# 00_Power.net
KiCad netlist of a schematic drawn in Altium Designer
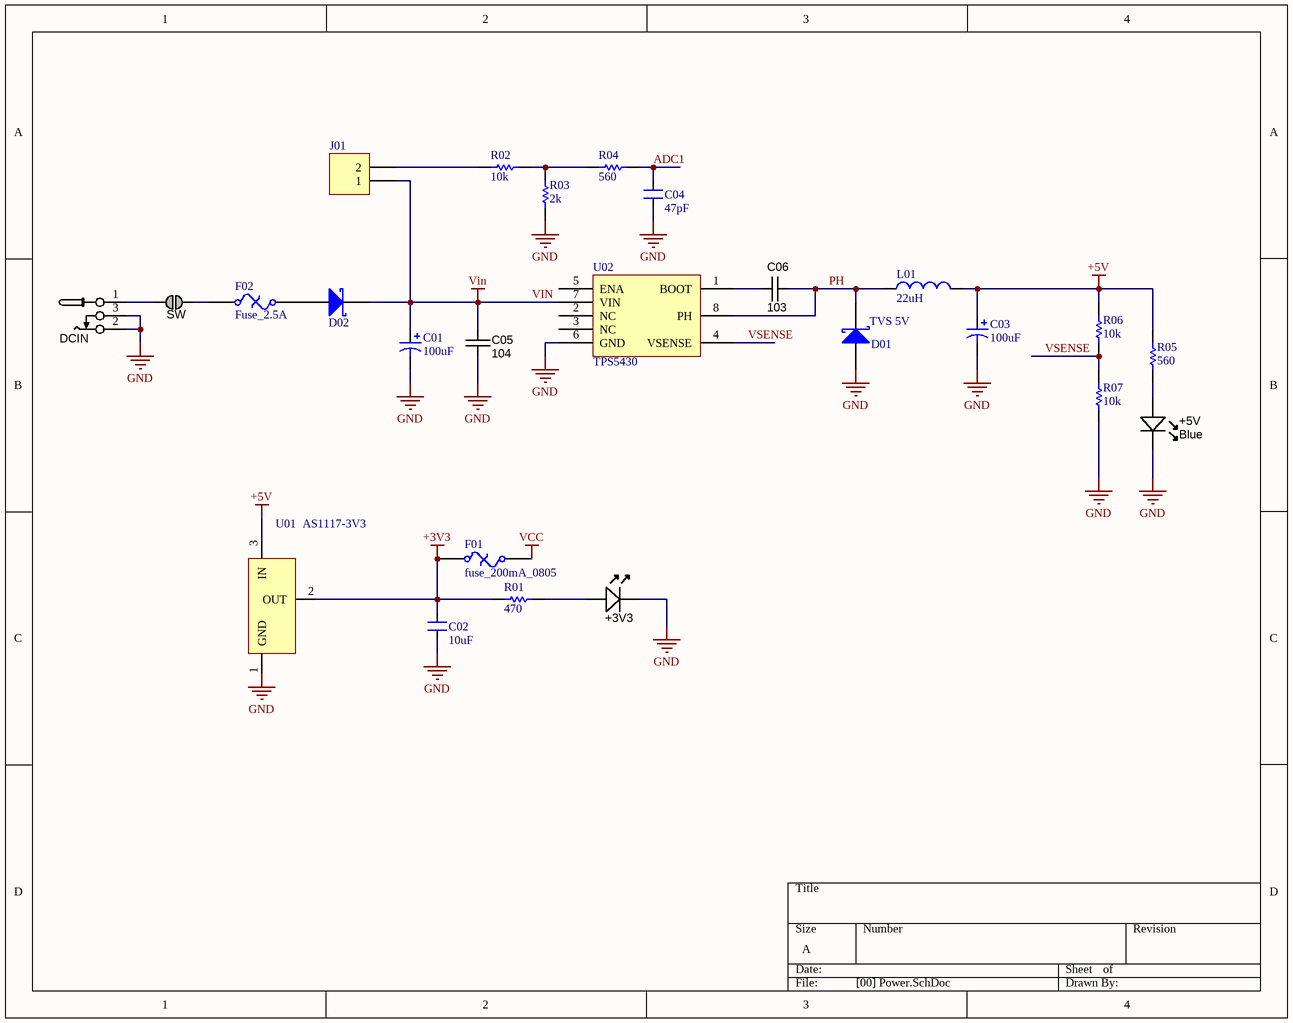
[diagram p0: [00] Power.SchDoc]

(export (version "E")
  (design (tool "Eeschema 10.0.6"))
  (components
    (comp (ref "+3V3")
      (value "Blue")
      (footprint "LED-0805-K")
      (description "LED 0805 SMD Blue 100mcd 470nm")
      (libsource (lib "PBL - Light Sources") (part "LED_SMD_Blue_0805_100mcd"))
    )
    (comp (ref "+5V")
      (value "Blue")
      (footprint "LED-0805-K")
      (description "LED 0805 SMD Blue 100mcd 470nm")
      (fields (field (name "COLOR") "Blue"))
      (libsource (lib "PBL - Light Sources") (part "LED_SMD_Blue_0805_100mcd"))
    )
    (comp (ref "C01")
      (value "100uF")
      (footprint "CAPE3.5-5.0MM_Rad_10x14mm")
      (fields (field (name "Comment") "Cap"))
      (libsource (lib "Tuan") (part "Cap"))
    )
    (comp (ref "C02")
      (value "10uF")
      (footprint "CAPMP3528X210N")
      (fields (field (name "Comment") "Cap_10uF"))
      (libsource (lib "Tuan") (part "CAP NP"))
    )
    (comp (ref "C03")
      (value "100uF")
      (footprint "CAPE3.5-5.0MM_Rad_10x14mm")
      (fields (field (name "Comment") "Cap"))
      (libsource (lib "Tuan") (part "Cap"))
    )
    (comp (ref "C04")
      (value "47pF")
      (footprint "CAPC1608N")
      (fields (field (name "Comment") "Cap_103_0603"))
      (libsource (lib "Tuan") (part "CAP NP"))
    )
    (comp (ref "C05")
      (value "104")
      (footprint "CAPC1608N")
      (description "Capacitor SMD Cer 1nF 10% 100V X7R 0603")
      (fields (field (name "TOLERANCE") "±10%") (field (name "Comment") "approved sub OK"))
      (libsource (lib "PBL - Capacitors") (part "CAPC_1n_0603_100V"))
    )
    (comp (ref "C06")
      (value "103")
      (footprint "CAPC1608N")
      (description "Capacitor SMD Cer 1nF 10% 100V X7R 0603")
      (fields (field (name "TOLERANCE") "±10%") (field (name "Comment") "approved sub OK"))
      (libsource (lib "PBL - Capacitors") (part "CAPC_1n_0603_100V"))
    )
    (comp (ref "D01") (value "TVS 5V") (footprint "SMD diode") (libsource (lib "Tuan") (part "Diode")))
    (comp (ref "D02") (value "SS14") (footprint "DO-214AC") (libsource (lib "Tuan") (part "Diode")))
    (comp (ref "DCIN")
      (value "CONN_PWR_JACK_2.1x5.5mm")
      (footprint "CONN_PWR_JACK_2.1x5.5mm")
      (description "Power Connector, THT, 2.1mm ID, 5.5mm OD")
      (libsource (lib "PBL - Connectors") (part "CONN_PWR_JACK_2.1x5.5mm"))
    )
    (comp (ref "F01")
      (value "fuse_200mA_0805")
      (footprint "SMD 1206")
      (description "Thermal Fuse")
      (fields (field (name "PUBLISHER") "Altium Limited"))
      (libsource (lib "Miscellaneous Devices") (part "Fuse Thermal"))
    )
    (comp (ref "F02")
      (value "Fuse_2.5A")
      (footprint "FUSE_SR-5-BK")
      (description "Thermal Fuse")
      (fields (field (name "PUBLISHER") "Altium Limited"))
      (libsource (lib "Miscellaneous Devices") (part "Fuse Thermal"))
    )
    (comp (ref "J01")
      (value "Header 2")
      (footprint "HDR1X2")
      (description "Header, 2-Pin")
      (fields (field (name "PUBLISHER") "Altium Limited"))
      (libsource (lib "Miscellaneous Connectors") (part "Header 2"))
    )
    (comp (ref "L01")
      (value "22uH")
      (footprint "Inductor 12x12x6")
      (fields (field (name "Comment") "Inductor"))
      (libsource (lib "Tuan") (part "Inductor"))
    )
    (comp (ref "R01")
      (value "470")
      (footprint "RESC1608N_F")
      (fields (field (name "Comment") "Res_560_0603"))
      (libsource (lib "Tuan") (part "Res"))
    )
    (comp (ref "R02")
      (value "10k")
      (footprint "RESC1608N_F")
      (fields (field (name "Comment") "Res_10k_0603"))
      (libsource (lib "Tuan") (part "Res"))
    )
    (comp (ref "R03")
      (value "2k")
      (footprint "RESC1608N_F")
      (fields (field (name "Comment") "Res_2k_0603"))
      (libsource (lib "Tuan") (part "Res"))
    )
    (comp (ref "R04")
      (value "560")
      (footprint "RESC1608N_F")
      (fields (field (name "Comment") "Res_560_0603"))
      (libsource (lib "Tuan") (part "Res"))
    )
    (comp (ref "R05")
      (value "560")
      (footprint "RESC1608N_ZERO")
      (fields (field (name "Comment") "Res"))
      (libsource (lib "Tuan") (part "Res"))
    )
    (comp (ref "R06")
      (value "10k")
      (footprint "RESC1608N_ZERO")
      (fields (field (name "Comment") "Res"))
      (libsource (lib "Tuan") (part "Res"))
    )
    (comp (ref "R07")
      (value "10k")
      (footprint "RESC1608N_ZERO")
      (fields (field (name "Comment") "Res"))
      (libsource (lib "Tuan") (part "Res"))
    )
    (comp (ref "SW")
      (value "Jumper")
      (footprint "JUMP1")
      (description "SMD jumper")
      (libsource (lib "PBL - Pads and Jumpers") (part "JUMP1"))
    )
    (comp (ref "U01") (value "AS1117-3V3") (footprint "SOT223-4N") (libsource (lib "Tuan") (part "AS1117")))
    (comp (ref "U02")
      (value "TPS5430")
      (footprint "SOIC127P600X175-8AN")
      (libsource (lib "Tuan") (part "TPS5430"))
    )
  )
  (nets
    (net (code "1") (name "+3V3") (class "Default")
      (node (ref "C02") (pin "2") (pinfunction "2_2") (pintype "passive"))
      (node (ref "F01") (pin "1") (pinfunction "1_1") (pintype "passive"))
      (node (ref "R01") (pin "2") (pinfunction "2_2") (pintype "passive"))
      (node (ref "U01") (pin "2") (pinfunction "OUT_2") (pintype "power_in"))
    )
    (net (code "2") (name "+5V") (class "Default")
      (node (ref "C03") (pin "1") (pinfunction "1_1") (pintype "passive"))
      (node (ref "L01") (pin "2") (pinfunction "2_2") (pintype "passive"))
      (node (ref "R05") (pin "2") (pinfunction "2_2") (pintype "passive"))
      (node (ref "R06") (pin "2") (pinfunction "2_2") (pintype "passive"))
      (node (ref "U01") (pin "3") (pinfunction "IN_3") (pintype "power_in"))
    )
    (net (code "3") (name "/ADC1") (class "Default")
      (node (ref "C04") (pin "2") (pinfunction "2_2") (pintype "passive"))
      (node (ref "R04") (pin "1") (pinfunction "1_1") (pintype "passive"))
    )
    (net (code "4") (name "/PH") (class "Default")
      (node (ref "C06") (pin "2") (pintype "passive"))
      (node (ref "D01") (pin "2") (pinfunction "K_2") (pintype "passive"))
      (node (ref "L01") (pin "1") (pinfunction "1_1") (pintype "passive"))
      (node (ref "U02") (pin "8") (pinfunction "PH_8") (pintype "power_in"))
    )
    (net (code "5") (name "/VSENSE") (class "Default")
      (node (ref "R06") (pin "1") (pinfunction "1_1") (pintype "passive"))
      (node (ref "R07") (pin "2") (pinfunction "2_2") (pintype "passive"))
      (node (ref "U02") (pin "4") (pinfunction "VSENSE_4") (pintype "power_in"))
    )
    (net (code "6") (name "GND") (class "Default")
      (node (ref "+3V3") (pin "K") (pinfunction "K_K") (pintype "passive"))
      (node (ref "+5V") (pin "K") (pinfunction "K_K") (pintype "passive"))
      (node (ref "C01") (pin "2") (pinfunction "2_2") (pintype "passive"))
      (node (ref "C02") (pin "1") (pinfunction "1_1") (pintype "passive"))
      (node (ref "C03") (pin "2") (pinfunction "2_2") (pintype "passive"))
      (node (ref "C04") (pin "1") (pinfunction "1_1") (pintype "passive"))
      (node (ref "C05") (pin "2") (pintype "passive"))
      (node (ref "D01") (pin "1") (pinfunction "A_1") (pintype "passive"))
      (node (ref "DCIN") (pin "2") (pinfunction "2_2") (pintype "passive"))
      (node (ref "DCIN") (pin "3") (pinfunction "3_3") (pintype "passive"))
      (node (ref "R03") (pin "1") (pinfunction "1_1") (pintype "passive"))
      (node (ref "R07") (pin "1") (pinfunction "1_1") (pintype "passive"))
      (node (ref "U01") (pin "1") (pinfunction "GND_1") (pintype "power_in"))
      (node (ref "U02") (pin "6") (pinfunction "GND_6") (pintype "power_in"))
    )
    (net (code "7") (name "Net-(+3V3-PadA)") (class "Default")
      (node (ref "+3V3") (pin "A") (pinfunction "A_A") (pintype "passive"))
      (node (ref "R01") (pin "1") (pinfunction "1_1") (pintype "passive"))
    )
    (net (code "8") (name "Net-(+5V-PadA)") (class "Default")
      (node (ref "+5V") (pin "A") (pinfunction "A_A") (pintype "passive"))
      (node (ref "R05") (pin "1") (pinfunction "1_1") (pintype "passive"))
    )
    (net (code "9") (name "Net-(D02-A)") (class "Default")
      (node (ref "D02") (pin "1") (pinfunction "A_1") (pintype "passive"))
      (node (ref "F02") (pin "1") (pinfunction "1_1") (pintype "passive"))
    )
    (net (code "10") (name "Net-(DCIN-Pad1)") (class "Default")
      (node (ref "DCIN") (pin "1") (pinfunction "1_1") (pintype "passive"))
      (node (ref "SW") (pin "2") (pintype "passive"))
    )
    (net (code "11") (name "Net-(F02-Pad2)") (class "Default")
      (node (ref "F02") (pin "2") (pinfunction "2_2") (pintype "passive"))
      (node (ref "SW") (pin "1") (pintype "passive"))
    )
    (net (code "12") (name "Net-(J01-Pad2)") (class "Default")
      (node (ref "J01") (pin "2") (pinfunction "2_2") (pintype "passive"))
      (node (ref "R02") (pin "2") (pinfunction "2_2") (pintype "passive"))
    )
    (net (code "13") (name "Net-(R02-Pad1)") (class "Default")
      (node (ref "R02") (pin "1") (pinfunction "1_1") (pintype "passive"))
      (node (ref "R03") (pin "2") (pinfunction "2_2") (pintype "passive"))
      (node (ref "R04") (pin "2") (pinfunction "2_2") (pintype "passive"))
    )
    (net (code "14") (name "Net-(U02-BOOT)") (class "Default")
      (node (ref "C06") (pin "1") (pintype "passive"))
      (node (ref "U02") (pin "1") (pinfunction "BOOT_1") (pintype "power_in"))
    )
    (net (code "15") (name "VCC") (class "Default")
      (node (ref "F01") (pin "2") (pinfunction "2_2") (pintype "passive"))
    )
    (net (code "16") (name "Vin") (class "Default")
      (node (ref "C01") (pin "1") (pinfunction "1_1") (pintype "passive"))
      (node (ref "C05") (pin "1") (pintype "passive"))
      (node (ref "D02") (pin "2") (pinfunction "K_2") (pintype "passive"))
      (node (ref "J01") (pin "1") (pinfunction "1_1") (pintype "passive"))
      (node (ref "U02") (pin "7") (pinfunction "VIN_7") (pintype "power_in"))
    )
    (net (code "17") (name "unconnected-(U02-ENA-Pad5)") (class "Default")
      (node (ref "U02") (pin "5") (pinfunction "ENA_5") (pintype "power_in"))
    )
    (net (code "18") (name "unconnected-(U02-NC-Pad2)") (class "Default")
      (node (ref "U02") (pin "2") (pinfunction "NC_2") (pintype "power_in"))
    )
    (net (code "19") (name "unconnected-(U02-NC-Pad3)") (class "Default")
      (node (ref "U02") (pin "3") (pinfunction "NC_3") (pintype "power_in"))
    )
  )
)
